# control_AC.net
KiCad netlist of a schematic drawn in EAGLE
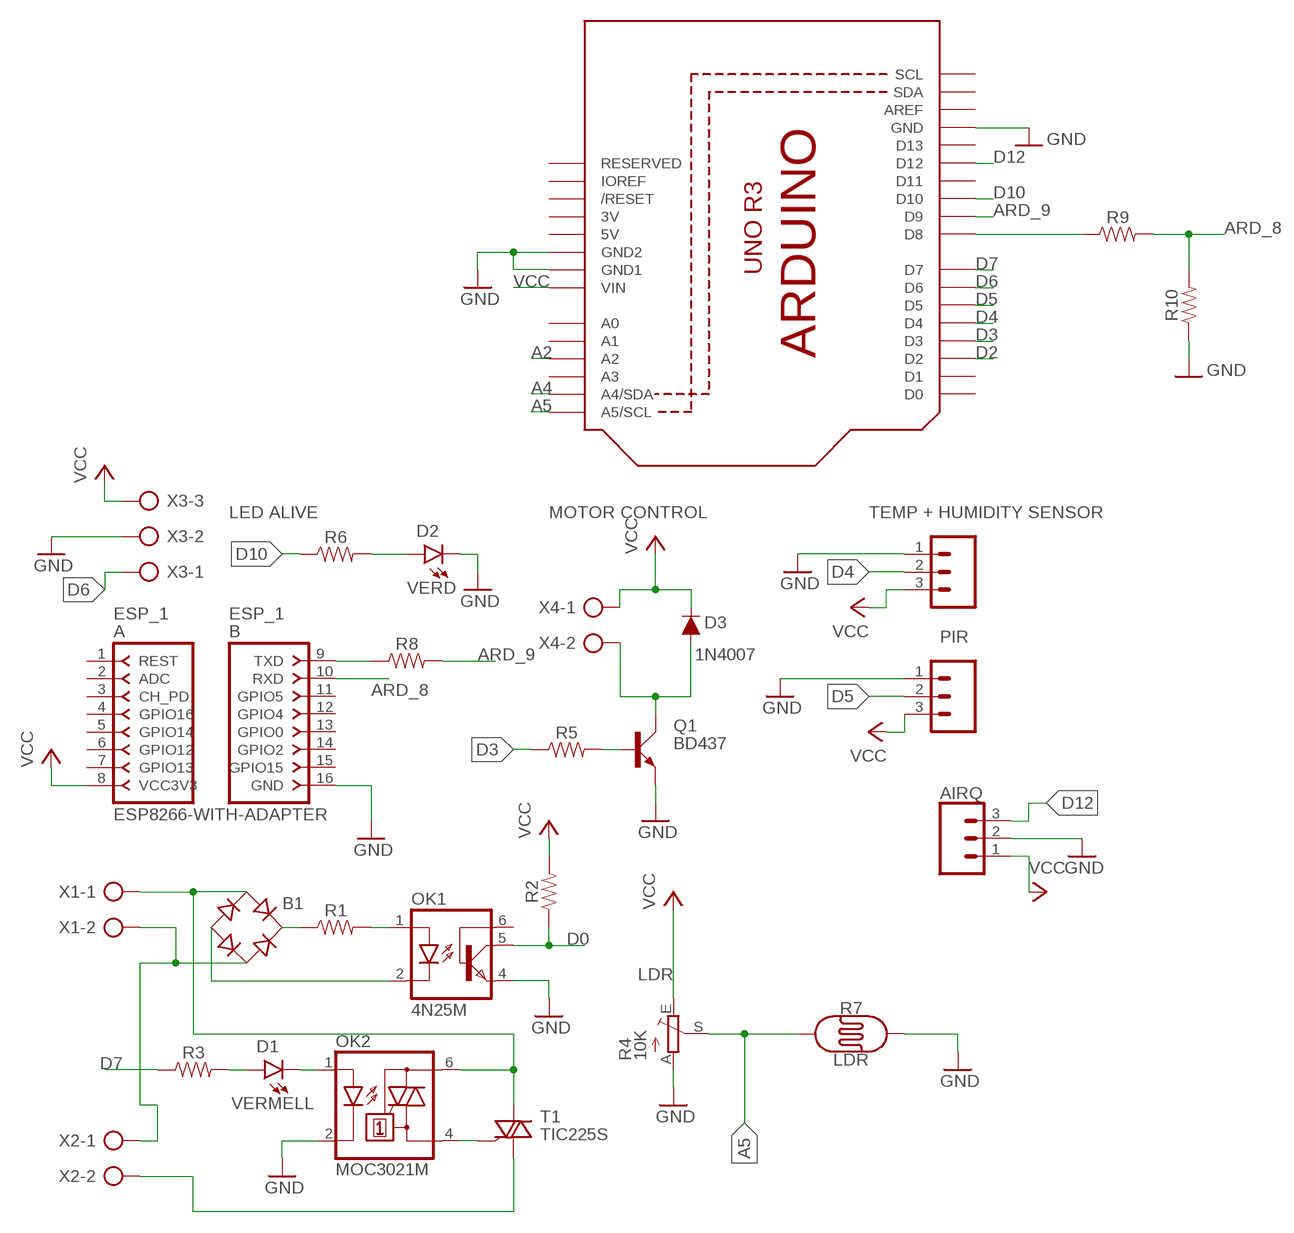
[diagram p0: schematic, sheet 1]

(export (version "E")
  (design (tool "Eeschema 10.0.6"))
  (components
    (comp (ref "AIRQ")
      (value "CONN_03")
      (footprint "eagle-import:1X03")
      (libsource (lib "eagle-import") (part "SparkFun-Connectors_513_CONN_03"))
    )
    (comp (ref "B1")
      (value "RB1A")
      (footprint "eagle-import:RB1A")
      (libsource (lib "eagle-import") (part "RB1A"))
    )
    (comp (ref "D1")
      (value "VERMELL")
      (footprint "eagle-import:LED-1206")
      (libsource (lib "eagle-import") (part "LED-RED1206"))
    )
    (comp (ref "D2")
      (value "VERD")
      (footprint "eagle-import:FKIT-LED-1206")
      (libsource (lib "eagle-import") (part "LED-FKIT-1206"))
    )
    (comp (ref "D3")
      (value "1N4007")
      (footprint "eagle-import:DIODE-1N4001")
      (libsource (lib "eagle-import") (part "DIODE-PTH"))
    )
    (comp (ref "ESP_1")
      (value "ESP8266-WITH-ADAPTER")
      (footprint "eagle-import:ESP8266-ADAPTER")
      (libsource (lib "eagle-import") (part "ESP8266-WITH-ADAPTER"))
    )
    (comp (ref "OK1")
      (value "4N25M")
      (footprint "eagle-import:DIL06")
      (fields (field (name "MPN") "4N25-M"))
      (libsource (lib "eagle-import") (part "4N?M25"))
    )
    (comp (ref "OK2")
      (value "MOC3021M")
      (footprint "eagle-import:DIL06")
      (fields (field (name "MF") "FAIRCHILD SEMICONDUCTOR") (field (name "MPN") "MOC3021-M"))
      (libsource (lib "eagle-import") (part "MOC30M21"))
    )
    (comp (ref "PIR")
      (value "455-1750-1-ND")
      (footprint "eagle-import:1X03")
      (libsource (lib "eagle-import") (part "CONN_03"))
    )
    (comp (ref "Q1")
      (value "BD437")
      (footprint "eagle-import:TO126AV")
      (libsource (lib "eagle-import") (part "BD437"))
    )
    (comp (ref "R1")
      (value "RESISTOR0805")
      (footprint "eagle-import:0805")
      (libsource (lib "eagle-import") (part "RESISTOR0805"))
    )
    (comp (ref "R2")
      (value "RESISTOR0805")
      (footprint "eagle-import:0805")
      (libsource (lib "eagle-import") (part "RESISTOR0805"))
    )
    (comp (ref "R3")
      (value "RESISTOR0805")
      (footprint "eagle-import:0805")
      (libsource (lib "eagle-import") (part "RESISTOR0805"))
    )
    (comp (ref "R4")
      (value "10K")
      (footprint "eagle-import:LI10")
      (libsource (lib "eagle-import") (part "TRIM_EU-LI10"))
    )
    (comp (ref "R5")
      (value "RESISTOR0805")
      (footprint "eagle-import:0805")
      (libsource (lib "eagle-import") (part "RESISTOR0805"))
    )
    (comp (ref "R6")
      (value "RESISTOR0805")
      (footprint "eagle-import:0805")
      (libsource (lib "eagle-import") (part "SparkFun-Resistors_532_RESISTOR0805"))
    )
    (comp (ref "R7")
      (value "LDR")
      (footprint "eagle-import:PHOTOCELL-KIT")
      (libsource (lib "eagle-import") (part "PHOTOCELLPTH-KIT"))
    )
    (comp (ref "R8")
      (value "RESISTOR0805")
      (footprint "eagle-import:0805")
      (libsource (lib "eagle-import") (part "SparkFun-Resistors_532_RESISTOR0805"))
    )
    (comp (ref "R9")
      (value "RESISTOR0805")
      (footprint "eagle-import:0805")
      (libsource (lib "eagle-import") (part "SparkFun-Resistors_532_RESISTOR0805"))
    )
    (comp (ref "R10")
      (value "RESISTOR0805")
      (footprint "eagle-import:0805")
      (libsource (lib "eagle-import") (part "SparkFun-Resistors_532_RESISTOR0805"))
    )
    (comp (ref "T1")
      (value "TIC225S")
      (footprint "eagle-import:TO220DS")
      (libsource (lib "eagle-import") (part "TIC225S"))
    )
    (comp (ref "TEMP+HUM")
      (value "455-1750-1-ND")
      (footprint "eagle-import:1X03")
      (libsource (lib "eagle-import") (part "CONN_03"))
    )
    (comp (ref "U2")
      (value "ARDUINOR3-DIMENSION")
      (footprint "eagle-import:ARDUINOR3")
      (libsource (lib "eagle-import") (part "ARDUINOR3-DIMENSION"))
    )
    (comp (ref "X1")
      (value "AK500/2")
      (footprint "eagle-import:AK500_2")
      (libsource (lib "eagle-import") (part "AK500/2"))
    )
    (comp (ref "X2")
      (value "AK500/2")
      (footprint "eagle-import:AK500_2")
      (libsource (lib "eagle-import") (part "AK500/2"))
    )
    (comp (ref "X3")
      (value "AK500/3")
      (footprint "eagle-import:AK500_3")
      (libsource (lib "eagle-import") (part "AK500/3"))
    )
    (comp (ref "X4")
      (value "AK500/2")
      (footprint "eagle-import:AK500_2")
      (libsource (lib "eagle-import") (part "AK500/2"))
    )
  )
  (nets
    (net (code "1") (name "/3V") (class "Default")
      (node (ref "U2") (pin "3V") (pinfunction "3V_3V") (pintype "power_in"))
    )
    (net (code "2") (name "/5V") (class "Default")
      (node (ref "U2") (pin "5V") (pinfunction "5V_5V") (pintype "power_in"))
    )
    (net (code "3") (name "/A2") (class "Default")
      (node (ref "U2") (pin "A2") (pinfunction "A2_A2") (pintype "bidirectional"))
    )
    (net (code "4") (name "/A4") (class "Default")
      (node (ref "U2") (pin "A4") (pinfunction "A4/SDA_A4") (pintype "bidirectional"))
    )
    (net (code "5") (name "/ARD_8") (class "Default")
      (node (ref "ESP_1") (pin "10") (pinfunction "RXD_10") (pintype "passive"))
      (node (ref "R10") (pin "2") (pinfunction "2_2") (pintype "passive"))
      (node (ref "R9") (pin "2") (pinfunction "2_2") (pintype "passive"))
    )
    (net (code "6") (name "/ARD_9") (class "Default")
      (node (ref "R8") (pin "2") (pinfunction "2_2") (pintype "passive"))
      (node (ref "U2") (pin "D9") (pinfunction "D9_D9") (pintype "bidirectional"))
    )
    (net (code "7") (name "/D0") (class "Default")
      (node (ref "OK1") (pin "5") (pinfunction "COL_5") (pintype "passive"))
      (node (ref "R2") (pin "1") (pinfunction "1_1") (pintype "passive"))
    )
    (net (code "8") (name "/D2") (class "Default")
      (node (ref "U2") (pin "D2") (pinfunction "D2_D2") (pintype "bidirectional"))
    )
    (net (code "9") (name "/D7") (class "Default")
      (node (ref "R3") (pin "1") (pinfunction "1_1") (pintype "passive"))
      (node (ref "U2") (pin "D7") (pinfunction "D7_D7") (pintype "bidirectional"))
    )
    (net (code "10") (name "A5") (class "Default")
      (node (ref "R4") (pin "S") (pinfunction "S_S") (pintype "passive"))
      (node (ref "R7") (pin "1") (pinfunction "P$1_1") (pintype "bidirectional"))
      (node (ref "U2") (pin "A5") (pinfunction "A5/SCL_A5") (pintype "bidirectional"))
    )
    (net (code "11") (name "D3") (class "Default")
      (node (ref "R5") (pin "1") (pinfunction "1_1") (pintype "passive"))
      (node (ref "U2") (pin "D3") (pinfunction "D3_D3") (pintype "bidirectional"))
    )
    (net (code "12") (name "D4") (class "Default")
      (node (ref "TEMP+HUM") (pin "2") (pinfunction "2_2") (pintype "passive"))
      (node (ref "U2") (pin "D4") (pinfunction "D4_D4") (pintype "bidirectional"))
    )
    (net (code "13") (name "D5") (class "Default")
      (node (ref "PIR") (pin "2") (pinfunction "2_2") (pintype "passive"))
      (node (ref "U2") (pin "D5") (pinfunction "D5_D5") (pintype "bidirectional"))
    )
    (net (code "14") (name "D6") (class "Default")
      (node (ref "U2") (pin "D6") (pinfunction "D6_D6") (pintype "bidirectional"))
      (node (ref "X3") (pin "1") (pinfunction "KL_1") (pintype "passive"))
    )
    (net (code "15") (name "D10") (class "Default")
      (node (ref "R6") (pin "1") (pinfunction "1_1") (pintype "passive"))
      (node (ref "U2") (pin "D10") (pinfunction "D10_D10") (pintype "bidirectional"))
    )
    (net (code "16") (name "D12") (class "Default")
      (node (ref "AIRQ") (pin "3") (pinfunction "3_3") (pintype "passive"))
      (node (ref "U2") (pin "D12") (pinfunction "D12_D12") (pintype "bidirectional"))
    )
    (net (code "17") (name "GND") (class "Default")
      (node (ref "AIRQ") (pin "2") (pinfunction "2_2") (pintype "passive"))
      (node (ref "D2") (pin "C") (pinfunction "C_C") (pintype "passive"))
      (node (ref "ESP_1") (pin "16") (pinfunction "GND_16") (pintype "passive"))
      (node (ref "OK1") (pin "4") (pinfunction "EMI_4") (pintype "passive"))
      (node (ref "OK2") (pin "2") (pinfunction "C_2") (pintype "passive"))
      (node (ref "PIR") (pin "1") (pinfunction "1_1") (pintype "passive"))
      (node (ref "Q1") (pin "E") (pinfunction "E_E") (pintype "passive"))
      (node (ref "R10") (pin "1") (pinfunction "1_1") (pintype "passive"))
      (node (ref "R4") (pin "A") (pinfunction "A_A") (pintype "passive"))
      (node (ref "R7") (pin "2") (pinfunction "P$2_2") (pintype "bidirectional"))
      (node (ref "TEMP+HUM") (pin "1") (pinfunction "1_1") (pintype "passive"))
      (node (ref "U2") (pin "GND") (pinfunction "GND_GND") (pintype "power_in"))
      (node (ref "U2") (pin "GND1") (pinfunction "GND1_GND1") (pintype "power_in"))
      (node (ref "U2") (pin "GND2") (pinfunction "GND2_GND2") (pintype "power_in"))
      (node (ref "X3") (pin "2") (pinfunction "KL_2") (pintype "passive"))
    )
    (net (code "18") (name "Net-(B1-Pad+)") (class "Default")
      (node (ref "B1") (pin "+") (pinfunction "+_+") (pintype "passive"))
      (node (ref "R1") (pin "1") (pinfunction "1_1") (pintype "passive"))
    )
    (net (code "19") (name "Net-(D1-PadA)") (class "Default")
      (node (ref "D1") (pin "A") (pinfunction "A_A") (pintype "passive"))
      (node (ref "R3") (pin "2") (pinfunction "2_2") (pintype "passive"))
    )
    (net (code "20") (name "Net-(D2-PadA)") (class "Default")
      (node (ref "D2") (pin "A") (pinfunction "A_A") (pintype "passive"))
      (node (ref "R6") (pin "2") (pinfunction "2_2") (pintype "passive"))
    )
    (net (code "21") (name "Net-(ESP_1-TXD)") (class "Default")
      (node (ref "ESP_1") (pin "9") (pinfunction "TXD_9") (pintype "passive"))
      (node (ref "R8") (pin "1") (pinfunction "1_1") (pintype "passive"))
    )
    (net (code "22") (name "Net-(OK1-A)") (class "Default")
      (node (ref "OK1") (pin "1") (pinfunction "A_1") (pintype "passive"))
      (node (ref "R1") (pin "2") (pinfunction "2_2") (pintype "passive"))
    )
    (net (code "23") (name "Net-(OK1-C)") (class "Default")
      (node (ref "B1") (pin "-") (pinfunction "-_-") (pintype "passive"))
      (node (ref "OK1") (pin "2") (pinfunction "C_2") (pintype "passive"))
    )
    (net (code "24") (name "Net-(OK2-A)") (class "Default")
      (node (ref "D1") (pin "C") (pinfunction "C_C") (pintype "passive"))
      (node (ref "OK2") (pin "1") (pinfunction "A_1") (pintype "passive"))
    )
    (net (code "25") (name "Net-(OK2-A1)") (class "Default")
      (node (ref "OK2") (pin "4") (pinfunction "A1_4") (pintype "passive"))
      (node (ref "T1") (pin "G") (pinfunction "G_G") (pintype "passive"))
    )
    (net (code "26") (name "Net-(OK2-A2)") (class "Default")
      (node (ref "B1") (pin "AC1") (pinfunction "AC1_AC1") (pintype "passive"))
      (node (ref "OK2") (pin "6") (pinfunction "A2_6") (pintype "passive"))
      (node (ref "T1") (pin "A2") (pinfunction "A2_A2") (pintype "passive"))
      (node (ref "X1") (pin "1") (pinfunction "KL_1") (pintype "passive"))
    )
    (net (code "27") (name "Net-(Q1-PadB)") (class "Default")
      (node (ref "Q1") (pin "B") (pinfunction "B_B") (pintype "passive"))
      (node (ref "R5") (pin "2") (pinfunction "2_2") (pintype "passive"))
    )
    (net (code "28") (name "Net-(R9-Pad1)") (class "Default")
      (node (ref "R9") (pin "1") (pinfunction "1_1") (pintype "passive"))
      (node (ref "U2") (pin "D8") (pinfunction "D8_D8") (pintype "bidirectional"))
    )
    (net (code "29") (name "Net-(X1B-KL)") (class "Default")
      (node (ref "B1") (pin "AC2") (pinfunction "AC2_AC2") (pintype "passive"))
      (node (ref "X1") (pin "2") (pinfunction "KL_2") (pintype "passive"))
      (node (ref "X2") (pin "1") (pinfunction "KL_1") (pintype "passive"))
    )
    (net (code "30") (name "Net-(X2B-KL)") (class "Default")
      (node (ref "T1") (pin "A1") (pinfunction "A1_A1") (pintype "passive"))
      (node (ref "X2") (pin "2") (pinfunction "KL_2") (pintype "passive"))
    )
    (net (code "31") (name "Net-(X4B-KL)") (class "Default")
      (node (ref "D3") (pin "A") (pinfunction "A_A") (pintype "passive"))
      (node (ref "Q1") (pin "C") (pinfunction "C_C") (pintype "passive"))
      (node (ref "X4") (pin "2") (pinfunction "KL_2") (pintype "passive"))
    )
    (net (code "32") (name "VCC") (class "Default")
      (node (ref "AIRQ") (pin "1") (pinfunction "1_1") (pintype "passive"))
      (node (ref "D3") (pin "C") (pinfunction "C_C") (pintype "passive"))
      (node (ref "ESP_1") (pin "8") (pinfunction "VCC3V3_8") (pintype "passive"))
      (node (ref "PIR") (pin "3") (pinfunction "3_3") (pintype "passive"))
      (node (ref "R2") (pin "2") (pinfunction "2_2") (pintype "passive"))
      (node (ref "R4") (pin "E") (pinfunction "E_E") (pintype "passive"))
      (node (ref "TEMP+HUM") (pin "3") (pinfunction "3_3") (pintype "passive"))
      (node (ref "U2") (pin "VIN") (pinfunction "VIN_VIN") (pintype "power_in"))
      (node (ref "X3") (pin "3") (pinfunction "KL_3") (pintype "passive"))
      (node (ref "X4") (pin "1") (pinfunction "KL_1") (pintype "passive"))
    )
    (net (code "33") (name "unconnected-(ESP_1-ADC-Pad2)") (class "Default")
      (node (ref "ESP_1") (pin "2") (pinfunction "ADC_2") (pintype "passive"))
    )
    (net (code "34") (name "unconnected-(ESP_1-CH_PD-Pad3)") (class "Default")
      (node (ref "ESP_1") (pin "3") (pinfunction "CH_PD_3") (pintype "passive"))
    )
    (net (code "35") (name "unconnected-(ESP_1-GPIO0-Pad13)") (class "Default")
      (node (ref "ESP_1") (pin "13") (pinfunction "GPIO0_13") (pintype "passive"))
    )
    (net (code "36") (name "unconnected-(ESP_1-GPIO2-Pad14)") (class "Default")
      (node (ref "ESP_1") (pin "14") (pinfunction "GPIO2_14") (pintype "passive"))
    )
    (net (code "37") (name "unconnected-(ESP_1-GPIO4-Pad12)") (class "Default")
      (node (ref "ESP_1") (pin "12") (pinfunction "GPIO4_12") (pintype "passive"))
    )
    (net (code "38") (name "unconnected-(ESP_1-GPIO5-Pad11)") (class "Default")
      (node (ref "ESP_1") (pin "11") (pinfunction "GPIO5_11") (pintype "passive"))
    )
    (net (code "39") (name "unconnected-(ESP_1-GPIO12-Pad6)") (class "Default")
      (node (ref "ESP_1") (pin "6") (pinfunction "GPIO12_6") (pintype "passive"))
    )
    (net (code "40") (name "unconnected-(ESP_1-GPIO13-Pad7)") (class "Default")
      (node (ref "ESP_1") (pin "7") (pinfunction "GPIO13_7") (pintype "passive"))
    )
    (net (code "41") (name "unconnected-(ESP_1-GPIO14-Pad5)") (class "Default")
      (node (ref "ESP_1") (pin "5") (pinfunction "GPIO14_5") (pintype "passive"))
    )
    (net (code "42") (name "unconnected-(ESP_1-GPIO15-Pad15)") (class "Default")
      (node (ref "ESP_1") (pin "15") (pinfunction "GPIO15_15") (pintype "passive"))
    )
    (net (code "43") (name "unconnected-(ESP_1-GPIO16-Pad4)") (class "Default")
      (node (ref "ESP_1") (pin "4") (pinfunction "GPIO16_4") (pintype "passive"))
    )
    (net (code "44") (name "unconnected-(ESP_1-REST-Pad1)") (class "Default")
      (node (ref "ESP_1") (pin "1") (pinfunction "REST_1") (pintype "passive"))
    )
    (net (code "45") (name "unconnected-(OK1-BAS-Pad6)") (class "Default")
      (node (ref "OK1") (pin "6") (pinfunction "BAS_6") (pintype "passive"))
    )
    (net (code "46") (name "unconnected-(U2-PadA0)") (class "Default")
      (node (ref "U2") (pin "A0") (pinfunction "A0_A0") (pintype "bidirectional"))
    )
    (net (code "47") (name "unconnected-(U2-PadA1)") (class "Default")
      (node (ref "U2") (pin "A1") (pinfunction "A1_A1") (pintype "bidirectional"))
    )
    (net (code "48") (name "unconnected-(U2-PadA3)") (class "Default")
      (node (ref "U2") (pin "A3") (pinfunction "A3_A3") (pintype "bidirectional"))
    )
    (net (code "49") (name "unconnected-(U2-PadAREF)") (class "Default")
      (node (ref "U2") (pin "AREF") (pinfunction "AREF_AREF") (pintype "bidirectional"))
    )
    (net (code "50") (name "unconnected-(U2-PadD0)") (class "Default")
      (node (ref "U2") (pin "D0") (pinfunction "D0_D0") (pintype "bidirectional"))
    )
    (net (code "51") (name "unconnected-(U2-PadD1)") (class "Default")
      (node (ref "U2") (pin "D1") (pinfunction "D1_D1") (pintype "bidirectional"))
    )
    (net (code "52") (name "unconnected-(U2-PadD11)") (class "Default")
      (node (ref "U2") (pin "D11") (pinfunction "D11_D11") (pintype "bidirectional"))
    )
    (net (code "53") (name "unconnected-(U2-PadD13)") (class "Default")
      (node (ref "U2") (pin "D13") (pinfunction "D13_D13") (pintype "bidirectional"))
    )
    (net (code "54") (name "unconnected-(U2-PadIOREF)") (class "Default")
      (node (ref "U2") (pin "IOREF") (pinfunction "IOREF_IOREF") (pintype "output"))
    )
    (net (code "55") (name "unconnected-(U2-PadRESERVED)") (class "Default")
      (node (ref "U2") (pin "RESERVED") (pinfunction "RESERVED_RESERVED") (pintype "no_connect"))
    )
    (net (code "56") (name "unconnected-(U2-PadSCL)") (class "Default")
      (node (ref "U2") (pin "SCL") (pinfunction "SCL_SCL") (pintype "bidirectional"))
    )
    (net (code "57") (name "unconnected-(U2-PadSDA)") (class "Default")
      (node (ref "U2") (pin "SDA") (pinfunction "SDA_SDA") (pintype "bidirectional"))
    )
    (net (code "58") (name "unconnected-(U2-{slash}RESET-PadRESET)") (class "Default")
      (node (ref "U2") (pin "RESET") (pinfunction "/RESET_RESET") (pintype "bidirectional"))
    )
  )
)
